# E17-04-CONNECTORS.net
KiCad netlist of a schematic drawn in Altium Designer
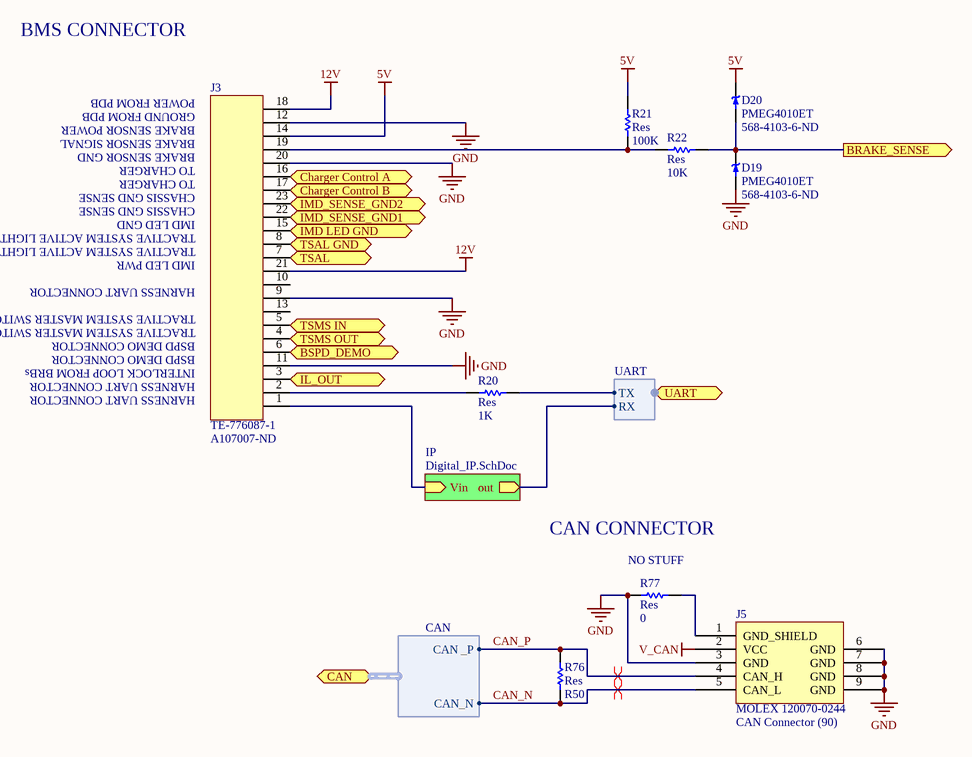
[diagram p0: E17-04-CONNECTORS.SchDoc]

(export (version "E")
  (design (tool "Eeschema 10.0.6"))
  (components
    (comp (ref "D19")
      (value "PMEG4010ET")
      (footprint "SOT23-3")
      (description "SCHOTTKY RECT 40V 1A SOT-23")
      (fields (field (name "SUPPLIER PART NUMBER 1") "568-4103-6-ND"))
      (libsource (lib "Diodes") (part "PMEG4010ET"))
    )
    (comp (ref "D20")
      (value "PMEG4010ET")
      (footprint "SOT23-3")
      (description "SCHOTTKY RECT 40V 1A SOT-23")
      (fields (field (name "SUPPLIER PART NUMBER 1") "568-4103-6-ND"))
      (libsource (lib "Diodes") (part "PMEG4010ET"))
    )
    (comp (ref "J3")
      (value "TE-776087-1")
      (footprint "TE-776087-1")
      (description "CONN HDR RTANG 23POS W/GASKT TIN")
      (fields (field (name "SUPPLIER PART NUMBER 1") "A107007-ND"))
      (libsource (lib "Connectors and Headers") (part "TE-776087-1"))
    )
    (comp (ref "J5")
      (value "CAN Connector (90)")
      (footprint "CAN Connector (90)")
      (libsource (lib "Molex_CAN_Connector") (part "CAN Connector (90)"))
    )
    (comp (ref "R20")
      (value "Res")
      (footprint "2012[0805]")
      (description "Surface Mount Resistor")
      (fields (field (name "ALTIUM_VALUE") "1K") (field (name "PUBLISHER") "Altium Limited"))
      (libsource (lib "Resistors") (part "Res"))
    )
    (comp (ref "R21")
      (value "Res")
      (footprint "2012[0805]")
      (description "Surface Mount Resistor")
      (fields (field (name "ALTIUM_VALUE") "100K") (field (name "PUBLISHER") "Altium Limited"))
      (libsource (lib "Resistors") (part "Res"))
    )
    (comp (ref "R22")
      (value "Res")
      (footprint "2012[0805]")
      (description "Surface Mount Resistor")
      (fields (field (name "ALTIUM_VALUE") "10K") (field (name "PUBLISHER") "Altium Limited"))
      (libsource (lib "Resistors") (part "Res"))
    )
    (comp (ref "R76")
      (value "Res")
      (footprint "2012[0805]")
      (description "Surface Mount Resistor")
      (fields (field (name "ALTIUM_VALUE") "R50") (field (name "PUBLISHER") "Altium Limited"))
      (libsource (lib "Resistors") (part "Res"))
    )
    (comp (ref "R77")
      (value "Res")
      (footprint "2012[0805]")
      (description "Surface Mount Resistor")
      (fields (field (name "ALTIUM_VALUE") "0") (field (name "PUBLISHER") "Altium Limited"))
      (libsource (lib "Resistors") (part "Res"))
    )
  )
  (nets
    (net (code "3") (name "/BRAKE_SENSE") (class "Default")
      (node (ref "D19") (pin "3") (pinfunction "3_3") (pintype "passive"))
      (node (ref "D20") (pin "1") (pinfunction "1_1") (pintype "passive"))
      (node (ref "R22") (pin "2") (pinfunction "2_2") (pintype "passive"))
    )
    (net (code "4") (name "/BSPD_DEMO") (class "Default") (node (ref "J3") (pin "6") (pintype "passive")))
    (net (code "5") (name "/CAN_N") (class "Default")
      (node (ref "J5") (pin "5") (pinfunction "CAN_L_5") (pintype "passive"))
      (node (ref "R76") (pin "1") (pinfunction "1_1") (pintype "passive"))
    )
    (net (code "6") (name "/CAN_P") (class "Default")
      (node (ref "J5") (pin "4") (pinfunction "CAN_H_4") (pintype "passive"))
      (node (ref "R76") (pin "2") (pinfunction "2_2") (pintype "passive"))
    )
    (net (code "7") (name "/Charger Control A") (class "Default")
      (node (ref "J3") (pin "16") (pintype "passive"))
    )
    (net (code "8") (name "/Charger Control B") (class "Default")
      (node (ref "J3") (pin "17") (pintype "passive"))
    )
    (net (code "9") (name "/IL_OUT") (class "Default") (node (ref "J3") (pin "3") (pintype "passive")))
    (net (code "10") (name "/IMD LED GND") (class "Default") (node (ref "J3") (pin "15") (pintype "passive")))
    (net (code "11") (name "/IMD_SENSE_GND1") (class "Default")
      (node (ref "J3") (pin "22") (pintype "passive"))
    )
    (net (code "12") (name "/IMD_SENSE_GND2") (class "Default")
      (node (ref "J3") (pin "23") (pintype "passive"))
    )
    (net (code "14") (name "/TSAL") (class "Default") (node (ref "J3") (pin "7") (pintype "passive")))
    (net (code "15") (name "/TSAL GND") (class "Default") (node (ref "J3") (pin "8") (pintype "passive")))
    (net (code "16") (name "/TSMS IN") (class "Default") (node (ref "J3") (pin "5") (pintype "passive")))
    (net (code "17") (name "/TSMS OUT") (class "Default") (node (ref "J3") (pin "4") (pintype "passive")))
    (net (code "18") (name "/TX") (class "Default")
      (node (ref "R20") (pin "2") (pinfunction "2_2") (pintype "passive"))
    )
    (net (code "19") (name "/Vin") (class "Default") (node (ref "J3") (pin "1") (pintype "passive")))
    (net (code "22") (name "5V") (class "Default")
      (node (ref "D20") (pin "3") (pinfunction "3_3") (pintype "passive"))
      (node (ref "J3") (pin "14") (pintype "passive"))
      (node (ref "R21") (pin "1") (pinfunction "1_1") (pintype "passive"))
    )
    (net (code "23") (name "12V") (class "Default")
      (node (ref "J3") (pin "18") (pintype "passive"))
      (node (ref "J3") (pin "21") (pintype "passive"))
    )
    (net (code "24") (name "GND") (class "Default")
      (node (ref "D19") (pin "1") (pinfunction "1_1") (pintype "passive"))
      (node (ref "J3") (pin "11") (pintype "passive"))
      (node (ref "J3") (pin "12") (pintype "passive"))
      (node (ref "J3") (pin "20") (pintype "passive"))
      (node (ref "J3") (pin "9") (pintype "passive"))
      (node (ref "J5") (pin "3") (pinfunction "GND_3") (pintype "passive"))
      (node (ref "J5") (pin "6") (pinfunction "GND_6") (pintype "passive"))
      (node (ref "J5") (pin "7") (pinfunction "GND_7") (pintype "passive"))
      (node (ref "J5") (pin "8") (pinfunction "GND_8") (pintype "passive"))
      (node (ref "J5") (pin "9") (pinfunction "GND_9") (pintype "passive"))
      (node (ref "R77") (pin "2") (pinfunction "2_2") (pintype "passive"))
    )
    (net (code "25") (name "Net-(J3-Pad2)") (class "Default")
      (node (ref "J3") (pin "2") (pintype "passive"))
      (node (ref "R20") (pin "1") (pinfunction "1_1") (pintype "passive"))
    )
    (net (code "26") (name "Net-(J3-Pad19)") (class "Default")
      (node (ref "J3") (pin "19") (pintype "passive"))
      (node (ref "R21") (pin "2") (pinfunction "2_2") (pintype "passive"))
      (node (ref "R22") (pin "1") (pinfunction "1_1") (pintype "passive"))
    )
    (net (code "27") (name "Net-(J5-GND_SHIELD)") (class "Default")
      (node (ref "J5") (pin "1") (pinfunction "GND_SHIELD_1") (pintype "passive"))
      (node (ref "R77") (pin "1") (pinfunction "1_1") (pintype "passive"))
    )
    (net (code "28") (name "V_CAN") (class "Default")
      (node (ref "J5") (pin "2") (pinfunction "VCC_2") (pintype "passive"))
    )
    (net (code "29") (name "unconnected-(J3-Pad10)") (class "Default")
      (node (ref "J3") (pin "10") (pintype "passive"))
    )
    (net (code "30") (name "unconnected-(J3-Pad13)") (class "Default")
      (node (ref "J3") (pin "13") (pintype "passive"))
    )
  )
)
